# Power.net
KiCad netlist of a schematic drawn in Altium Designer
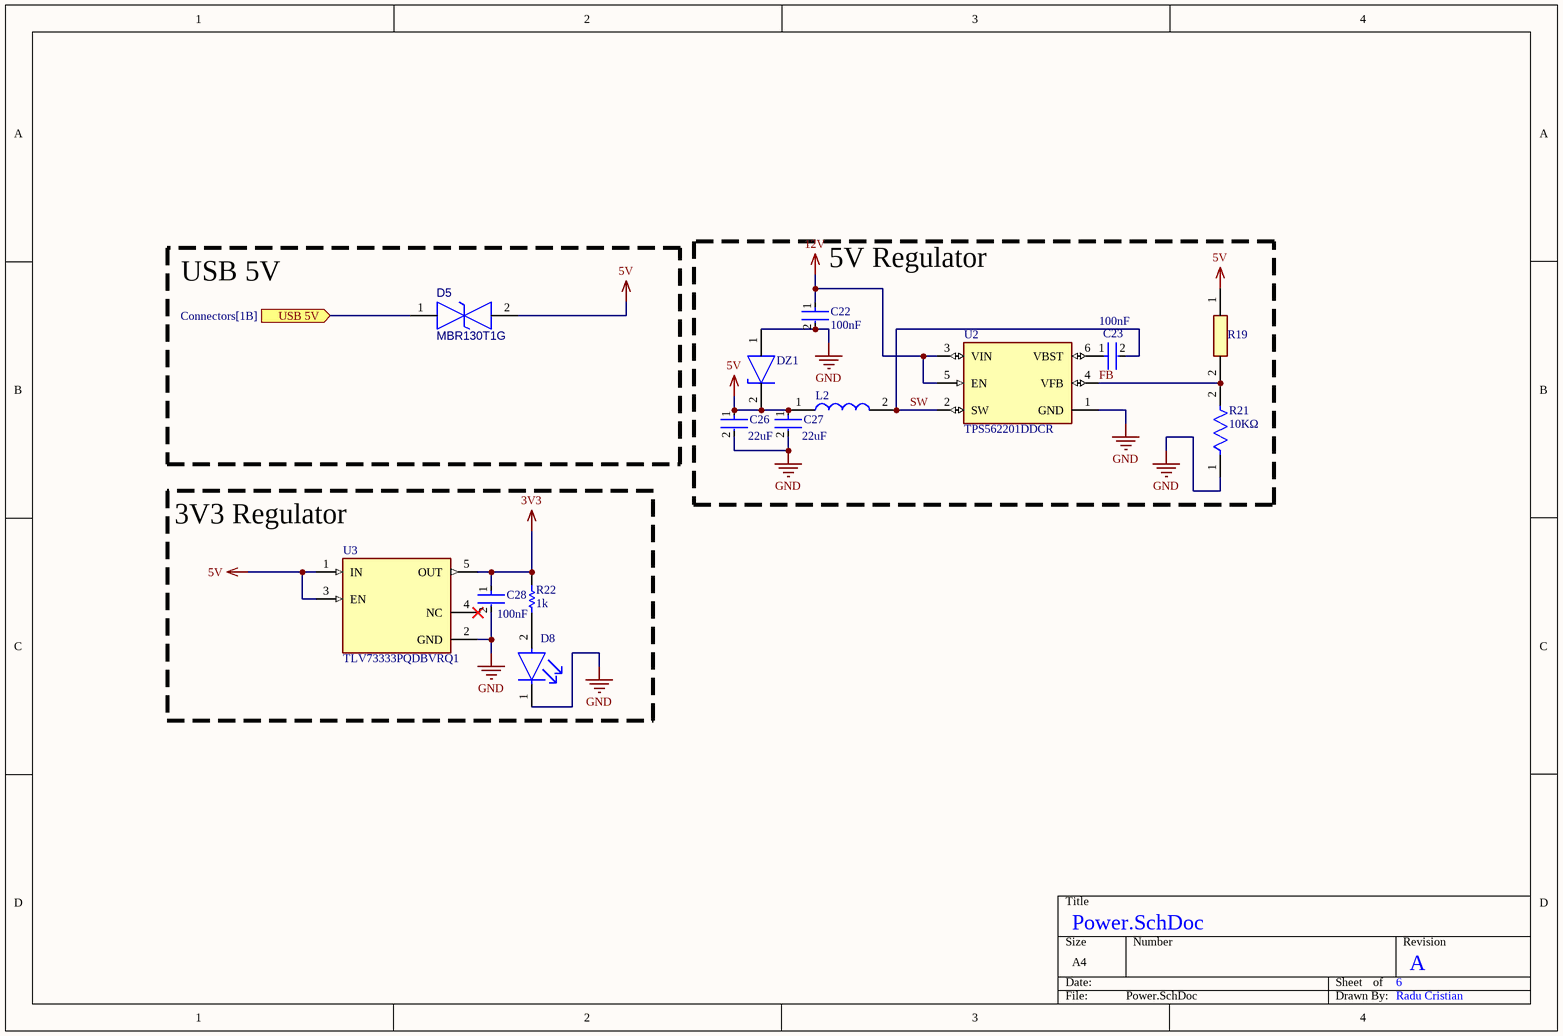
[diagram p0: Power.SchDoc]

(export (version "E")
  (design (tool "Eeschema 10.0.6"))
  (components
    (comp (ref "C22")
      (value "CC0603JRX7R9BB104")
      (footprint "FP-CC0603-DA-MFG")
      (description "CAP CER 0.1UF 50V X7R 0603")
      (fields (field (name "CAPACITANCE") "100nF") (field (name "TOLERANCE") "5%"))
      (libsource (lib "Altium Content Vault") (part "02cd4be3c70576c341d710602a673aa"))
    )
    (comp (ref "C23")
      (value "CC0603JRX7R9BB104")
      (footprint "FP-CC0603-DA-MFG")
      (description "CAP CER 0.1UF 50V X7R 0603")
      (fields (field (name "CAPACITANCE") "100nF") (field (name "TOLERANCE") "5%"))
      (libsource (lib "Altium Content Vault") (part "02cd4be3c70576c341d710602a673aa"))
    )
    (comp (ref "C26")
      (value "GRM188R61A226ME15D")
      (footprint "FP-GRM188-0_2-IPC_C")
      (description "Chip Multilayer Ceramic Capacitors for General Purpose, 0603, 22uF, X5R, 15%, 20%, 10V")
      (fields (field (name "TOLERANCE") "20%") (field (name "CAPACITANCE") "22uF"))
      (libsource (lib "Altium Content Vault") (part "11868f565c42a9108669ba33697ecf6"))
    )
    (comp (ref "C27")
      (value "GRM188R61A226ME15D")
      (footprint "FP-GRM188-0_2-IPC_C")
      (description "Chip Multilayer Ceramic Capacitors for General Purpose, 0603, 22uF, X5R, 15%, 20%, 10V")
      (fields (field (name "TOLERANCE") "20%") (field (name "CAPACITANCE") "22uF"))
      (libsource (lib "Altium Content Vault") (part "11868f565c42a9108669ba33697ecf6"))
    )
    (comp (ref "C28")
      (value "CC0603JRX7R9BB104")
      (footprint "FP-CC0603-DA-IPC_A")
      (description "CAP CER 0.1UF 50V X7R 0603")
      (fields (field (name "CAPACITANCE") "100nF") (field (name "TOLERANCE") "5%"))
      (libsource (lib "Altium Content Vault") (part "02cd4be3c70576c341d710602a673aa"))
    )
    (comp (ref "D5")
      (value "MBR130T1G")
      (footprint "ONSC-SOD-123-2-425-04_V")
      (description "Rectifier Diode, Schottky, 1 Phase, 1 Element, 1A, 30V V(RRM), Silicon")
      (libsource (lib "ART-TU Cluj-Napoca") (part "SMBJ5.0CA-TR"))
    )
    (comp (ref "D8")
      (value "KPT-3216ID")
      (footprint "FP-APTD3216CGCK-MFG")
      (description "LED RED CLEAR 2SMD")
      (libsource (lib "Altium Content Vault") (part "8706943c75ba83719d021d2fdc84c58"))
    )
    (comp (ref "DZ1")
      (value "VTVS5V0ASMF-M3-08")
      (footprint "FP-S8-V-3915_01-001-MFG")
      (description "VTVS5V0ASMF-M3-08 Esd Protection Diode Smf Do219Ab5%; 5V; ir5 A; ip43A; p400W; cd2095Pf")
      (libsource (lib "Altium Content Vault") (part "d386f69c7d770905792c16b93fa31a7"))
    )
    (comp (ref "L2")
      (value "LCXHF3030QKT4R7MNR")
      (footprint "SamacSys:LCXHF3030QKT4R7MNR")
      (description "Inductor")
      (libsource (lib "*") (part "LCXHF3030QKT4R7MNR"))
    )
    (comp (ref "R19")
      (value "ERA-3ARB563V")
      (footprint "SamacSys:ERA3AEB101V")
      (description "Resistor")
      (fields (field (name "MOUSER PART NUMBER") "667-ERA-3ARB563V"))
      (libsource (lib "*") (part "ERA-3ARB563V"))
    )
    (comp (ref "R21")
      (value "CRGP0603F10K")
      (footprint "FP-CRGP0603-IPC_C")
      (description "CRGP 0603 10K 1%")
      (fields
        (field (name "OCTOPART") "https://octopart.com/crgp0603f10k-te+connectivity-91018721")
        (field (name "TOLERANCE") "0.01")
        (field (name "RESISTANCE") "10KΩ")
      )
      (libsource (lib "Altium Content Vault") (part "1029c3af85768c4190bb7ad29bc67b5"))
    )
    (comp (ref "R22")
      (value "ERJ-6ENF1001V")
      (footprint "RESC2013X70X40ML20T20")
      (description "Chip Resistor, 1 KOhm, +/- 1%, 0.125 W, -55 to 155 degC, 0805 (2012 Metric), RoHS, Tape and Reel")
      (fields (field (name "MANUFACTURER") "Panasonic") (field (name "PARAMETER 1") "1k"))
      (libsource (lib "Altium Content Vault") (part "RES-2"))
    )
    (comp (ref "U2")
      (value "TPS562201DDCR")
      (footprint "FP-DDC0006A-IPC_C")
      (description "IC REG BUCK ADJ 2A TSOT23-6")
      (libsource (lib "Altium Content Vault") (part "957e164956730ea4bf6293280af19fc"))
    )
    (comp (ref "U3")
      (value "TLV73333PQDBVRQ1")
      (footprint "FP-DBV0005A-IPC_A")
      (description "IC REG LINEAR 3.3V 300MA SOT23-5")
      (libsource (lib "Altium Content Vault") (part "9fe5a7569a672cc344d83ad3dd2d204"))
    )
  )
  (nets
    (net (code "1") (name "/FB") (class "Default")
      (node (ref "R19") (pin "2") (pinfunction "2_2") (pintype "passive"))
      (node (ref "R21") (pin "2") (pinfunction "2_2") (pintype "passive"))
      (node (ref "U2") (pin "4") (pinfunction "VFB_4") (pintype "bidirectional"))
    )
    (net (code "2") (name "/SW") (class "Default")
      (node (ref "C23") (pin "2") (pinfunction "2_2") (pintype "passive"))
      (node (ref "L2") (pin "2") (pinfunction "2_2") (pintype "passive"))
      (node (ref "U2") (pin "2") (pinfunction "SW_2") (pintype "bidirectional"))
    )
    (net (code "3") (name "/USB 5V") (class "Default")
      (node (ref "D5") (pin "1") (pinfunction "1_1") (pintype "passive"))
    )
    (net (code "4") (name "3V3") (class "Default")
      (node (ref "C28") (pin "1") (pinfunction "1_1") (pintype "passive"))
      (node (ref "R22") (pin "1") (pinfunction "1_1") (pintype "passive"))
      (node (ref "U3") (pin "5") (pinfunction "OUT_5") (pintype "output"))
    )
    (net (code "5") (name "5V") (class "Default")
      (node (ref "C26") (pin "1") (pinfunction "1_1") (pintype "passive"))
      (node (ref "C27") (pin "1") (pinfunction "1_1") (pintype "passive"))
      (node (ref "D5") (pin "2") (pinfunction "2_2") (pintype "passive"))
      (node (ref "DZ1") (pin "2") (pinfunction "C_2") (pintype "passive"))
      (node (ref "L2") (pin "1") (pinfunction "1_1") (pintype "passive"))
      (node (ref "R19") (pin "1") (pinfunction "1_1") (pintype "passive"))
      (node (ref "U3") (pin "1") (pinfunction "IN_1") (pintype "input"))
      (node (ref "U3") (pin "3") (pinfunction "EN_3") (pintype "input"))
    )
    (net (code "6") (name "12V") (class "Default")
      (node (ref "C22") (pin "1") (pinfunction "1_1") (pintype "passive"))
      (node (ref "U2") (pin "3") (pinfunction "VIN_3") (pintype "bidirectional"))
      (node (ref "U2") (pin "5") (pinfunction "EN_5") (pintype "input"))
    )
    (net (code "7") (name "GND") (class "Default")
      (node (ref "C22") (pin "2") (pinfunction "2_2") (pintype "passive"))
      (node (ref "C26") (pin "2") (pinfunction "2_2") (pintype "passive"))
      (node (ref "C27") (pin "2") (pinfunction "2_2") (pintype "passive"))
      (node (ref "C28") (pin "2") (pinfunction "2_2") (pintype "passive"))
      (node (ref "D8") (pin "1") (pinfunction "C_1") (pintype "passive"))
      (node (ref "DZ1") (pin "1") (pinfunction "A_1") (pintype "passive"))
      (node (ref "R21") (pin "1") (pinfunction "1_1") (pintype "passive"))
      (node (ref "U2") (pin "1") (pinfunction "GND_1") (pintype "power_in"))
      (node (ref "U3") (pin "2") (pinfunction "GND_2") (pintype "power_in"))
    )
    (net (code "8") (name "Net-(D8-A)") (class "Default")
      (node (ref "D8") (pin "2") (pinfunction "A_2") (pintype "passive"))
      (node (ref "R22") (pin "2") (pinfunction "2_2") (pintype "passive"))
    )
    (net (code "9") (name "Net-(U2-VBST)") (class "Default")
      (node (ref "C23") (pin "1") (pinfunction "1_1") (pintype "passive"))
      (node (ref "U2") (pin "6") (pinfunction "VBST_6") (pintype "bidirectional"))
    )
    (net (code "10") (name "unconnected-(U3-NC-Pad4)") (class "Default")
      (node (ref "U3") (pin "4") (pinfunction "NC_4") (pintype "passive+no_connect"))
    )
  )
)
